# without_solar.net
KiCad netlist of a schematic drawn in EAGLE
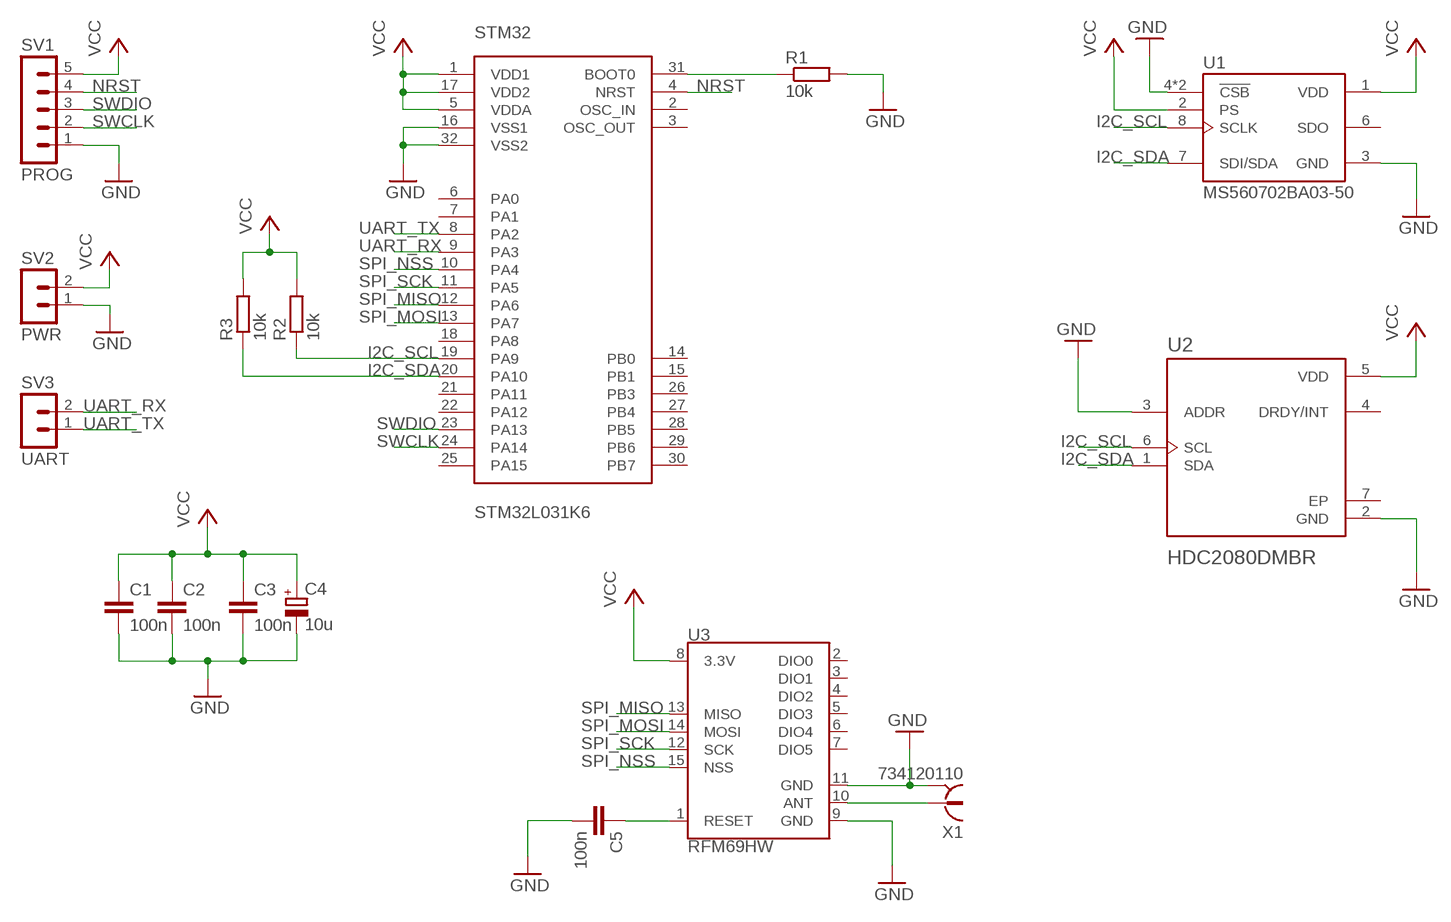
[diagram p0: schematic, sheet 1]

(export (version "E")
  (design (tool "Eeschema 10.0.6"))
  (components
    (comp (ref "C1")
      (value "100n")
      (footprint "eagle-import:C1206")
      (libsource (lib "eagle-import") (part "C-EUC1206"))
    )
    (comp (ref "C2")
      (value "100n")
      (footprint "eagle-import:C1206")
      (libsource (lib "eagle-import") (part "C-EUC1206"))
    )
    (comp (ref "C3")
      (value "100n")
      (footprint "eagle-import:C1206")
      (libsource (lib "eagle-import") (part "C-EUC1206"))
    )
    (comp (ref "C4")
      (value "10u")
      (footprint "eagle-import:UD-4X5,8_NICHICON")
      (libsource (lib "eagle-import") (part "CPOL-EUUD-4X5,8"))
    )
    (comp (ref "C5")
      (value "100n")
      (footprint "eagle-import:C1206")
      (libsource (lib "eagle-import") (part "C-EUC1206"))
    )
    (comp (ref "R1")
      (value "10k")
      (footprint "eagle-import:R0805")
      (libsource (lib "eagle-import") (part "R-EU_R0805"))
    )
    (comp (ref "R2")
      (value "10k")
      (footprint "eagle-import:R0805")
      (libsource (lib "eagle-import") (part "R-EU_R0805"))
    )
    (comp (ref "R3")
      (value "10k")
      (footprint "eagle-import:R0805")
      (libsource (lib "eagle-import") (part "R-EU_R0805"))
    )
    (comp (ref "STM32")
      (value "STM32L031K6")
      (footprint "eagle-import:LQFP32-7X7")
      (libsource (lib "eagle-import") (part "STM32L031K6"))
    )
    (comp (ref "SV1")
      (value "PROG")
      (footprint "eagle-import:MA05-1")
      (libsource (lib "eagle-import") (part "MA05-1"))
    )
    (comp (ref "SV2")
      (value "PWR")
      (footprint "eagle-import:MA02-1")
      (libsource (lib "eagle-import") (part "MA02-1"))
    )
    (comp (ref "SV3")
      (value "UART")
      (footprint "eagle-import:MA02-1")
      (libsource (lib "eagle-import") (part "MA02-1"))
    )
    (comp (ref "U1")
      (value "MS560702BA03-50")
      (footprint "eagle-import:SON125P300X500X100-8N")
      (fields (field (name "MF") "TE Connectivity"))
      (libsource (lib "eagle-import") (part "MS560702BA03-50"))
    )
    (comp (ref "U2")
      (value "HDC2080DMBR")
      (footprint "eagle-import:SON100P300X300X80-7N")
      (fields (field (name "MF") "Texas Instruments"))
      (libsource (lib "eagle-import") (part "HDC2080DMBR"))
    )
    (comp (ref "U3")
      (value "RFM69HW")
      (footprint "eagle-import:RFM69W-XXXS2")
      (libsource (lib "eagle-import") (part "RFM69HW"))
    )
    (comp (ref "X1")
      (value "734120110")
      (footprint "eagle-import:734120110")
      (libsource (lib "eagle-import") (part "734120110"))
    )
  )
  (nets
    (net (code "1") (name "/I2C_SCL") (class "Default")
      (node (ref "R2") (pin "1") (pinfunction "1_1") (pintype "passive"))
      (node (ref "STM32") (pin "19") (pinfunction "PA9_19") (pintype "bidirectional"))
      (node (ref "U1") (pin "8") (pinfunction "SCLK_8") (pintype "input"))
      (node (ref "U2") (pin "6") (pinfunction "SCL_6") (pintype "input"))
    )
    (net (code "2") (name "/I2C_SDA") (class "Default")
      (node (ref "R3") (pin "1") (pinfunction "1_1") (pintype "passive"))
      (node (ref "STM32") (pin "20") (pinfunction "PA10_20") (pintype "bidirectional"))
      (node (ref "U1") (pin "7") (pinfunction "SDI/SDA_7") (pintype "bidirectional"))
      (node (ref "U2") (pin "1") (pinfunction "SDA_1") (pintype "bidirectional"))
    )
    (net (code "3") (name "/NRST") (class "Default")
      (node (ref "STM32") (pin "4") (pinfunction "NRST_4") (pintype "bidirectional"))
      (node (ref "SV1") (pin "4") (pinfunction "4_4") (pintype "passive"))
    )
    (net (code "4") (name "/SPI_MISO") (class "Default")
      (node (ref "STM32") (pin "12") (pinfunction "PA6_12") (pintype "bidirectional"))
      (node (ref "U3") (pin "13") (pinfunction "MISO_13") (pintype "bidirectional"))
    )
    (net (code "5") (name "/SPI_MOSI") (class "Default")
      (node (ref "STM32") (pin "13") (pinfunction "PA7_13") (pintype "bidirectional"))
      (node (ref "U3") (pin "14") (pinfunction "MOSI_14") (pintype "input"))
    )
    (net (code "6") (name "/SPI_NSS") (class "Default")
      (node (ref "STM32") (pin "10") (pinfunction "PA4_10") (pintype "bidirectional"))
      (node (ref "U3") (pin "15") (pinfunction "NSS_15") (pintype "input"))
    )
    (net (code "7") (name "/SPI_SCK") (class "Default")
      (node (ref "STM32") (pin "11") (pinfunction "PA5_11") (pintype "bidirectional"))
      (node (ref "U3") (pin "12") (pinfunction "SCK_12") (pintype "input"))
    )
    (net (code "8") (name "/SWCLK") (class "Default")
      (node (ref "STM32") (pin "24") (pinfunction "PA14_24") (pintype "bidirectional"))
      (node (ref "SV1") (pin "2") (pinfunction "2_2") (pintype "passive"))
    )
    (net (code "9") (name "/SWDIO") (class "Default")
      (node (ref "STM32") (pin "23") (pinfunction "PA13_23") (pintype "bidirectional"))
      (node (ref "SV1") (pin "3") (pinfunction "3_3") (pintype "passive"))
    )
    (net (code "10") (name "/UART_RX") (class "Default")
      (node (ref "STM32") (pin "9") (pinfunction "PA3_9") (pintype "bidirectional"))
      (node (ref "SV3") (pin "2") (pinfunction "3_2") (pintype "passive"))
    )
    (net (code "11") (name "/UART_TX") (class "Default")
      (node (ref "STM32") (pin "8") (pinfunction "PA2_8") (pintype "bidirectional"))
      (node (ref "SV3") (pin "1") (pinfunction "2_1") (pintype "passive"))
    )
    (net (code "12") (name "GND") (class "Default")
      (node (ref "C1") (pin "2") (pinfunction "2_2") (pintype "passive"))
      (node (ref "C2") (pin "2") (pinfunction "2_2") (pintype "passive"))
      (node (ref "C3") (pin "2") (pinfunction "2_2") (pintype "passive"))
      (node (ref "C4") (pin "-") (pinfunction "-_-") (pintype "passive"))
      (node (ref "C5") (pin "2") (pinfunction "2_2") (pintype "passive"))
      (node (ref "R1") (pin "2") (pinfunction "2_2") (pintype "passive"))
      (node (ref "STM32") (pin "16") (pinfunction "VSS1_16") (pintype "bidirectional"))
      (node (ref "STM32") (pin "32") (pinfunction "VSS2_32") (pintype "bidirectional"))
      (node (ref "SV1") (pin "1") (pinfunction "1_1") (pintype "passive"))
      (node (ref "SV2") (pin "1") (pinfunction "2_1") (pintype "passive"))
      (node (ref "U1") (pin "3") (pinfunction "GND_3") (pintype "power_in"))
      (node (ref "U1") (pin "4") (pinfunction "~{CSB}_4") (pintype "input"))
      (node (ref "U1") (pin "5") (pinfunction "~{CSB}_5") (pintype "input"))
      (node (ref "U2") (pin "2") (pinfunction "GND_2") (pintype "power_in"))
      (node (ref "U2") (pin "3") (pinfunction "ADDR_3") (pintype "input"))
      (node (ref "U3") (pin "11") (pinfunction "GND_11") (pintype "power_in"))
      (node (ref "U3") (pin "9") (pinfunction "GND_9") (pintype "power_in"))
      (node (ref "X1") (pin "S@1") (pinfunction "2_S@1") (pintype "passive"))
      (node (ref "X1") (pin "S@2") (pinfunction "2_S@2") (pintype "passive"))
      (node (ref "X1") (pin "S@3") (pinfunction "2_S@3") (pintype "passive"))
    )
    (net (code "13") (name "Net-(STM32-BOOT0)") (class "Default")
      (node (ref "R1") (pin "1") (pinfunction "1_1") (pintype "passive"))
      (node (ref "STM32") (pin "31") (pinfunction "BOOT0_31") (pintype "bidirectional"))
    )
    (net (code "14") (name "Net-(U3-ANT)") (class "Default")
      (node (ref "U3") (pin "10") (pinfunction "ANT_10") (pintype "passive"))
      (node (ref "X1") (pin "1") (pinfunction "1_1") (pintype "passive"))
    )
    (net (code "15") (name "Net-(U3-RESET)") (class "Default")
      (node (ref "C5") (pin "1") (pinfunction "1_1") (pintype "passive"))
      (node (ref "U3") (pin "1") (pinfunction "RESET_1") (pintype "input"))
    )
    (net (code "16") (name "VCC") (class "Default")
      (node (ref "C1") (pin "1") (pinfunction "1_1") (pintype "passive"))
      (node (ref "C2") (pin "1") (pinfunction "1_1") (pintype "passive"))
      (node (ref "C3") (pin "1") (pinfunction "1_1") (pintype "passive"))
      (node (ref "C4") (pin "+") (pinfunction "+_+") (pintype "passive"))
      (node (ref "R2") (pin "2") (pinfunction "2_2") (pintype "passive"))
      (node (ref "R3") (pin "2") (pinfunction "2_2") (pintype "passive"))
      (node (ref "STM32") (pin "1") (pinfunction "VDD1_1") (pintype "bidirectional"))
      (node (ref "STM32") (pin "17") (pinfunction "VDD2_17") (pintype "bidirectional"))
      (node (ref "STM32") (pin "5") (pinfunction "VDDA_5") (pintype "bidirectional"))
      (node (ref "SV1") (pin "5") (pinfunction "5_5") (pintype "passive"))
      (node (ref "SV2") (pin "2") (pinfunction "3_2") (pintype "passive"))
      (node (ref "U1") (pin "1") (pinfunction "VDD_1") (pintype "power_in"))
      (node (ref "U1") (pin "2") (pinfunction "PS_2") (pintype "input"))
      (node (ref "U2") (pin "5") (pinfunction "VDD_5") (pintype "power_in"))
      (node (ref "U3") (pin "8") (pinfunction "3.3V_8") (pintype "power_in"))
    )
    (net (code "17") (name "unconnected-(STM32-OSC_IN-Pad2)") (class "Default")
      (node (ref "STM32") (pin "2") (pinfunction "OSC_IN_2") (pintype "bidirectional"))
    )
    (net (code "18") (name "unconnected-(STM32-OSC_OUT-Pad3)") (class "Default")
      (node (ref "STM32") (pin "3") (pinfunction "OSC_OUT_3") (pintype "bidirectional"))
    )
    (net (code "19") (name "unconnected-(STM32-PA0-Pad6)") (class "Default")
      (node (ref "STM32") (pin "6") (pinfunction "PA0_6") (pintype "bidirectional"))
    )
    (net (code "20") (name "unconnected-(STM32-PA1-Pad7)") (class "Default")
      (node (ref "STM32") (pin "7") (pinfunction "PA1_7") (pintype "bidirectional"))
    )
    (net (code "21") (name "unconnected-(STM32-PA8-Pad18)") (class "Default")
      (node (ref "STM32") (pin "18") (pinfunction "PA8_18") (pintype "bidirectional"))
    )
    (net (code "22") (name "unconnected-(STM32-PA11-Pad21)") (class "Default")
      (node (ref "STM32") (pin "21") (pinfunction "PA11_21") (pintype "bidirectional"))
    )
    (net (code "23") (name "unconnected-(STM32-PA12-Pad22)") (class "Default")
      (node (ref "STM32") (pin "22") (pinfunction "PA12_22") (pintype "bidirectional"))
    )
    (net (code "24") (name "unconnected-(STM32-PA15-Pad25)") (class "Default")
      (node (ref "STM32") (pin "25") (pinfunction "PA15_25") (pintype "bidirectional"))
    )
    (net (code "25") (name "unconnected-(STM32-PB0-Pad14)") (class "Default")
      (node (ref "STM32") (pin "14") (pinfunction "PB0_14") (pintype "bidirectional"))
    )
    (net (code "26") (name "unconnected-(STM32-PB1-Pad15)") (class "Default")
      (node (ref "STM32") (pin "15") (pinfunction "PB1_15") (pintype "bidirectional"))
    )
    (net (code "27") (name "unconnected-(STM32-PB3-Pad26)") (class "Default")
      (node (ref "STM32") (pin "26") (pinfunction "PB3_26") (pintype "bidirectional"))
    )
    (net (code "28") (name "unconnected-(STM32-PB4-Pad27)") (class "Default")
      (node (ref "STM32") (pin "27") (pinfunction "PB4_27") (pintype "bidirectional"))
    )
    (net (code "29") (name "unconnected-(STM32-PB5-Pad28)") (class "Default")
      (node (ref "STM32") (pin "28") (pinfunction "PB5_28") (pintype "bidirectional"))
    )
    (net (code "30") (name "unconnected-(STM32-PB6-Pad29)") (class "Default")
      (node (ref "STM32") (pin "29") (pinfunction "PB6_29") (pintype "bidirectional"))
    )
    (net (code "31") (name "unconnected-(STM32-PB7-Pad30)") (class "Default")
      (node (ref "STM32") (pin "30") (pinfunction "PB7_30") (pintype "bidirectional"))
    )
    (net (code "32") (name "unconnected-(U1-SDO-Pad6)") (class "Default")
      (node (ref "U1") (pin "6") (pinfunction "SDO_6") (pintype "output"))
    )
    (net (code "33") (name "unconnected-(U2-DRDY{slash}INT-Pad4)") (class "Default")
      (node (ref "U2") (pin "4") (pinfunction "DRDY/INT_4") (pintype "output"))
    )
    (net (code "34") (name "unconnected-(U2-EP-Pad7)") (class "Default")
      (node (ref "U2") (pin "7") (pinfunction "EP_7") (pintype "passive"))
    )
    (net (code "35") (name "unconnected-(U3-DIO0-Pad2)") (class "Default")
      (node (ref "U3") (pin "2") (pinfunction "DIO0_2") (pintype "bidirectional"))
    )
    (net (code "36") (name "unconnected-(U3-DIO1-Pad3)") (class "Default")
      (node (ref "U3") (pin "3") (pinfunction "DIO1_3") (pintype "bidirectional"))
    )
    (net (code "37") (name "unconnected-(U3-DIO2-Pad4)") (class "Default")
      (node (ref "U3") (pin "4") (pinfunction "DIO2_4") (pintype "bidirectional"))
    )
    (net (code "38") (name "unconnected-(U3-DIO3-Pad5)") (class "Default")
      (node (ref "U3") (pin "5") (pinfunction "DIO3_5") (pintype "bidirectional"))
    )
    (net (code "39") (name "unconnected-(U3-DIO4-Pad6)") (class "Default")
      (node (ref "U3") (pin "6") (pinfunction "DIO4_6") (pintype "bidirectional"))
    )
    (net (code "40") (name "unconnected-(U3-DIO5-Pad7)") (class "Default")
      (node (ref "U3") (pin "7") (pinfunction "DIO5_7") (pintype "bidirectional"))
    )
  )
)
